# Voltage_Regulator.net
KiCad netlist of a schematic drawn in Altium Designer
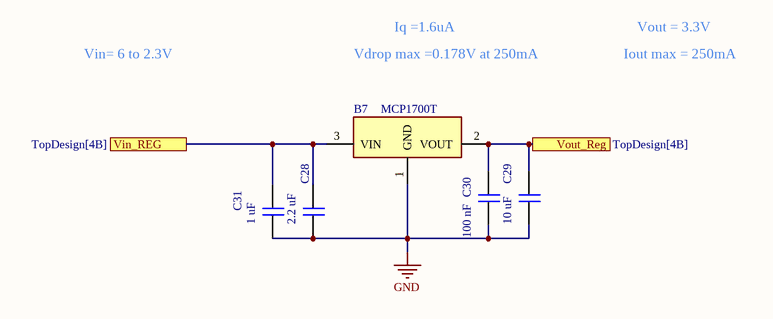
[diagram p0: Voltage_Regulator.SchDoc]

(export (version "E")
  (design (tool "Eeschema 10.0.6"))
  (components
    (comp (ref "B7")
      (value "MCP1700T")
      (footprint "MCP1700T-SOT23")
      (description "LDO voltage regulator 250mA Isupply 1.6uA")
      (fields (field (name "MPN") "Microchip"))
      (libsource (lib "Aptinex_devices") (part "MCP1700T-SOT23"))
    )
    (comp (ref "C28")
      (value "2.2 uF")
      (footprint "CAP_0603")
      (description "Cap SMD.")
      (libsource (lib "Aptinex_discrete") (part "Cap SMD"))
    )
    (comp (ref "C29")
      (value "10 uF")
      (footprint "CAP_0603")
      (description "Cap SMD.")
      (libsource (lib "Aptinex_discrete") (part "Cap SMD"))
    )
    (comp (ref "C30")
      (value "100 nF")
      (footprint "CAP_0603")
      (description "Cap SMD.")
      (libsource (lib "Aptinex_discrete") (part "Cap SMD"))
    )
    (comp (ref "C31")
      (value "1 uF")
      (footprint "CAP_0603")
      (description "Cap SMD.")
      (libsource (lib "Aptinex_discrete") (part "Cap SMD"))
    )
  )
  (nets
    (net (code "1") (name "/Vin_REG") (class "Default")
      (node (ref "B7") (pin "3") (pinfunction "VIN_3") (pintype "passive"))
      (node (ref "C28") (pin "2") (pinfunction "2_2") (pintype "passive"))
      (node (ref "C31") (pin "2") (pinfunction "2_2") (pintype "passive"))
    )
    (net (code "2") (name "/Vout_Reg") (class "Default")
      (node (ref "B7") (pin "2") (pinfunction "VOUT_2") (pintype "passive"))
      (node (ref "C29") (pin "2") (pinfunction "2_2") (pintype "passive"))
      (node (ref "C30") (pin "2") (pinfunction "2_2") (pintype "passive"))
    )
    (net (code "3") (name "GND") (class "Default")
      (node (ref "B7") (pin "1") (pinfunction "GND_1") (pintype "passive"))
      (node (ref "C28") (pin "1") (pinfunction "1_1") (pintype "passive"))
      (node (ref "C29") (pin "1") (pinfunction "1_1") (pintype "passive"))
      (node (ref "C30") (pin "1") (pinfunction "1_1") (pintype "passive"))
      (node (ref "C31") (pin "1") (pinfunction "1_1") (pintype "passive"))
    )
  )
)
